# MCU.net
KiCad netlist of a schematic drawn in Altium Designer
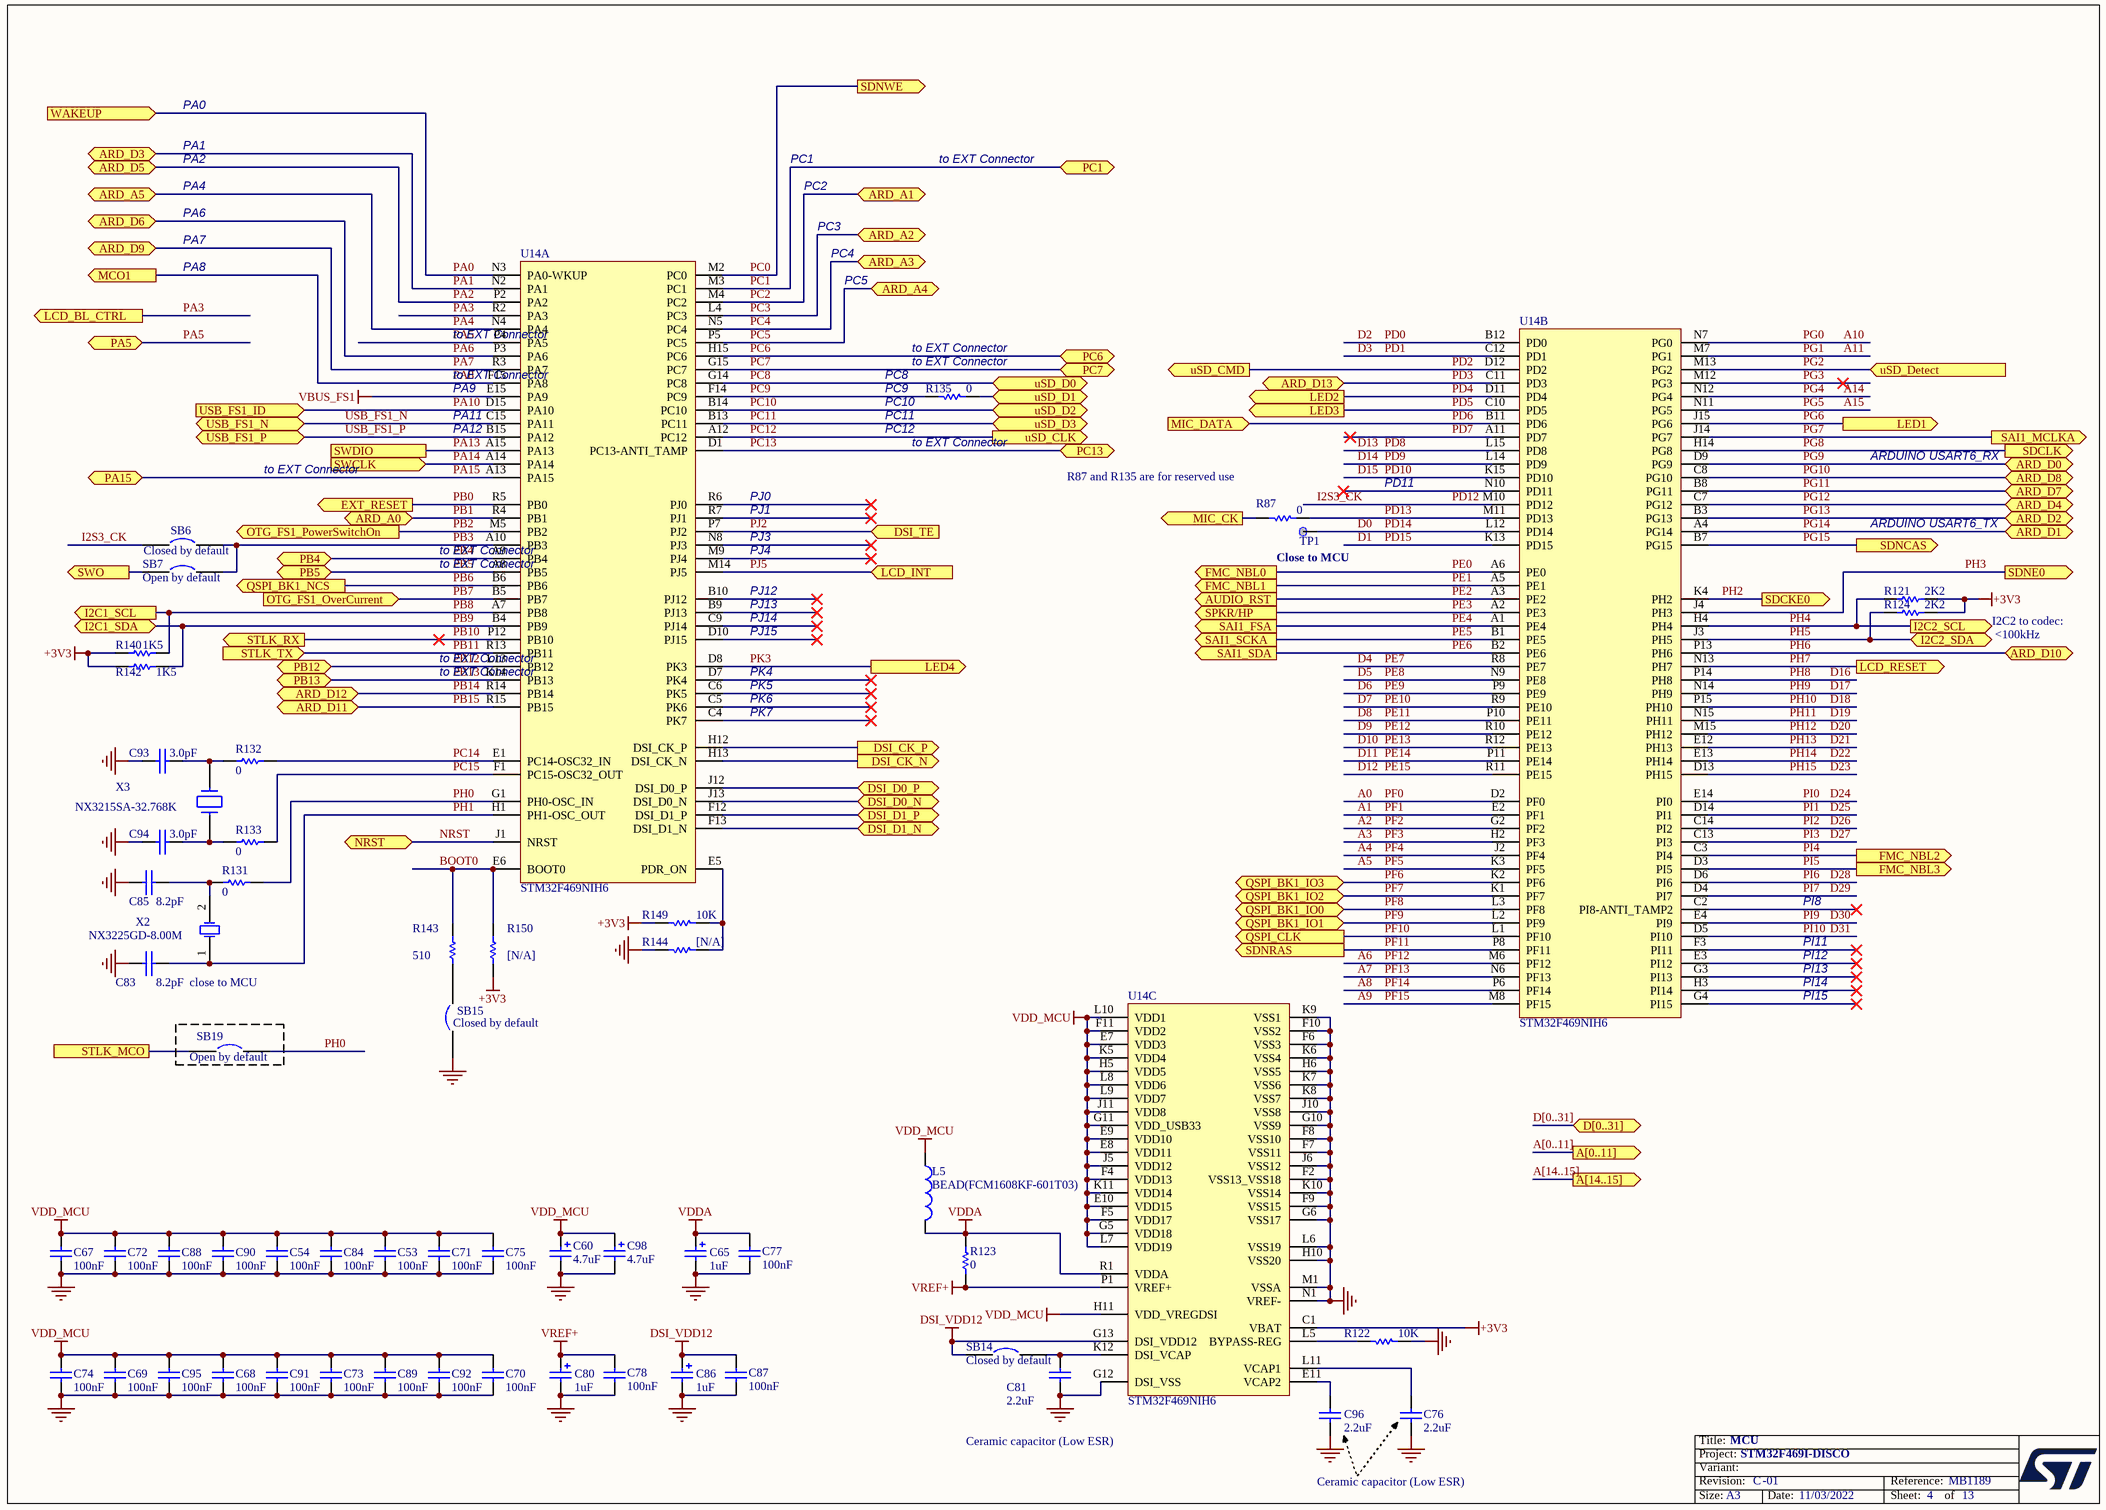
[diagram p0: MCU.SchDoc]

(export (version "E")
  (design (tool "Eeschema 10.0.6"))
  (components
    (comp (ref "C53")
      (value "100nF")
      (footprint "0402C")
      (description "Capacitor")
      (fields (field (name "PUBLISHER") "Altium Limited"))
      (libsource (lib "Miscellaneous Devices") (part "CAP"))
    )
    (comp (ref "C54")
      (value "100nF")
      (footprint "0402C")
      (description "Capacitor")
      (fields (field (name "PUBLISHER") "Altium Limited"))
      (libsource (lib "Miscellaneous Devices") (part "CAP"))
    )
    (comp (ref "C60")
      (value "4.7uF")
      (footprint "CPOL_TAJ-A_1206_H180")
      (description "Capacitor, Tantalum, 4.7uF, 16V, 10%, 4ohms, pkg Type_A (3216 metric), T=1.6mm")
      (libsource (lib "MB1189") (part "Cap_TAJA475K016R"))
    )
    (comp (ref "C65")
      (value "1uF")
      (footprint "CPOL_TAJ-A_1206_H180")
      (description "Capacitor, Tantalum, 1uF, 16V, 10%, 11Ohms, pkg Type_A (3216 metric), T=1.6mm")
      (libsource (lib "MB1189") (part "Cap_TAJA105K016RNJ"))
    )
    (comp (ref "C67")
      (value "100nF")
      (footprint "0402C")
      (description "Capacitor")
      (fields (field (name "PUBLISHER") "Altium Limited"))
      (libsource (lib "Miscellaneous Devices") (part "CAP"))
    )
    (comp (ref "C68")
      (value "100nF")
      (footprint "0402C")
      (description "Capacitor")
      (fields (field (name "PUBLISHER") "Altium Limited"))
      (libsource (lib "Miscellaneous Devices") (part "CAP"))
    )
    (comp (ref "C69")
      (value "100nF")
      (footprint "0402C")
      (description "Capacitor")
      (fields (field (name "PUBLISHER") "Altium Limited"))
      (libsource (lib "Miscellaneous Devices") (part "CAP"))
    )
    (comp (ref "C70")
      (value "100nF")
      (footprint "0402C")
      (description "Capacitor")
      (fields (field (name "PUBLISHER") "Altium Limited"))
      (libsource (lib "Miscellaneous Devices") (part "CAP"))
    )
    (comp (ref "C71")
      (value "100nF")
      (footprint "0402C")
      (description "Capacitor")
      (fields (field (name "PUBLISHER") "Altium Limited"))
      (libsource (lib "Miscellaneous Devices") (part "CAP"))
    )
    (comp (ref "C72")
      (value "100nF")
      (footprint "0402C")
      (description "Capacitor")
      (fields (field (name "PUBLISHER") "Altium Limited"))
      (libsource (lib "Miscellaneous Devices") (part "CAP"))
    )
    (comp (ref "C73")
      (value "100nF")
      (footprint "0402C")
      (description "Capacitor")
      (fields (field (name "PUBLISHER") "Altium Limited"))
      (libsource (lib "Miscellaneous Devices") (part "CAP"))
    )
    (comp (ref "C74")
      (value "100nF")
      (footprint "0402C")
      (description "Capacitor")
      (fields (field (name "PUBLISHER") "Altium Limited"))
      (libsource (lib "Miscellaneous Devices") (part "CAP"))
    )
    (comp (ref "C75")
      (value "100nF")
      (footprint "0402C")
      (description "Capacitor")
      (fields (field (name "PUBLISHER") "Altium Limited"))
      (libsource (lib "Miscellaneous Devices") (part "CAP"))
    )
    (comp (ref "C76")
      (value "2.2uF")
      (footprint "1206C")
      (description "Capacitor")
      (fields (field (name "PUBLISHER") "Altium Limited"))
      (libsource (lib "Miscellaneous Devices") (part "Cap"))
    )
    (comp (ref "C77")
      (value "100nF")
      (footprint "0402C")
      (description "Capacitor")
      (fields (field (name "PUBLISHER") "Altium Limited"))
      (libsource (lib "Miscellaneous Devices") (part "Cap"))
    )
    (comp (ref "C78")
      (value "100nF")
      (footprint "0402C")
      (description "Capacitor")
      (fields (field (name "PUBLISHER") "Altium Limited"))
      (libsource (lib "Miscellaneous Devices") (part "Cap"))
    )
    (comp (ref "C80")
      (value "1uF")
      (footprint "CPOL_TAJ-A_1206_H180")
      (description "Capacitor, Tantalum, 1uF, 16V, 10%, 11Ohms, pkg Type_A (3216 metric), T=1.6mm")
      (libsource (lib "MB1189") (part "Cap_TAJA105K016RNJ"))
    )
    (comp (ref "C81")
      (value "2.2uF")
      (footprint "1206C")
      (description "Capacitor")
      (fields (field (name "PUBLISHER") "Altium Limited"))
      (libsource (lib "Miscellaneous Devices") (part "Cap"))
    )
    (comp (ref "C83")
      (value "8.2pF")
      (footprint "0603C")
      (description "Capacitor")
      (libsource (lib "*") (part "CAP"))
    )
    (comp (ref "C84")
      (value "100nF")
      (footprint "0402C")
      (description "Capacitor")
      (fields (field (name "PUBLISHER") "Altium Limited"))
      (libsource (lib "Miscellaneous Devices") (part "CAP"))
    )
    (comp (ref "C85")
      (value "8.2pF")
      (footprint "0603C")
      (description "Capacitor")
      (libsource (lib "*") (part "CAP"))
    )
    (comp (ref "C86")
      (value "1uF")
      (footprint "CPOL_TAJ-A_1206_H180")
      (description "Capacitor, Tantalum, 1uF, 16V, 10%, 11Ohms, pkg Type_A (3216 metric), T=1.6mm")
      (libsource (lib "MB1189") (part "Cap_TAJA105K016RNJ"))
    )
    (comp (ref "C87")
      (value "100nF")
      (footprint "0402C")
      (description "Capacitor")
      (fields (field (name "PUBLISHER") "Altium Limited"))
      (libsource (lib "Miscellaneous Devices") (part "Cap"))
    )
    (comp (ref "C88")
      (value "100nF")
      (footprint "0402C")
      (description "Capacitor")
      (fields (field (name "PUBLISHER") "Altium Limited"))
      (libsource (lib "Miscellaneous Devices") (part "CAP"))
    )
    (comp (ref "C89")
      (value "100nF")
      (footprint "0402C")
      (description "Capacitor")
      (fields (field (name "PUBLISHER") "Altium Limited"))
      (libsource (lib "Miscellaneous Devices") (part "CAP"))
    )
    (comp (ref "C90")
      (value "100nF")
      (footprint "0402C")
      (description "Capacitor")
      (fields (field (name "PUBLISHER") "Altium Limited"))
      (libsource (lib "Miscellaneous Devices") (part "CAP"))
    )
    (comp (ref "C91")
      (value "100nF")
      (footprint "0402C")
      (description "Capacitor")
      (fields (field (name "PUBLISHER") "Altium Limited"))
      (libsource (lib "Miscellaneous Devices") (part "CAP"))
    )
    (comp (ref "C92")
      (value "100nF")
      (footprint "0402C")
      (description "Capacitor")
      (fields (field (name "PUBLISHER") "Altium Limited"))
      (libsource (lib "Miscellaneous Devices") (part "CAP"))
    )
    (comp (ref "C93")
      (value "3.0pF")
      (footprint "0603C")
      (description "Capacitor")
      (libsource (lib "") (part "CAP_1"))
    )
    (comp (ref "C94")
      (value "3.0pF")
      (footprint "0603C")
      (description "Capacitor")
      (libsource (lib "") (part "CAP_1"))
    )
    (comp (ref "C95")
      (value "100nF")
      (footprint "0402C")
      (description "Capacitor")
      (fields (field (name "PUBLISHER") "Altium Limited"))
      (libsource (lib "Miscellaneous Devices") (part "CAP"))
    )
    (comp (ref "C96")
      (value "2.2uF")
      (footprint "1206C")
      (description "Capacitor")
      (fields (field (name "PUBLISHER") "Altium Limited"))
      (libsource (lib "Miscellaneous Devices") (part "Cap"))
    )
    (comp (ref "C98")
      (value "4.7uF")
      (footprint "CPOL_TAJ-A_1206_H180")
      (description "Capacitor, Tantalum, 4.7uF, 16V, 10%, 4ohms, pkg Type_A (3216 metric), T=1.6mm")
      (libsource (lib "MB1189") (part "Cap_TAJA475K016R"))
    )
    (comp (ref "L5")
      (value "BEAD(FCM1608KF-601T03)")
      (footprint "0603L")
      (description "Inductor")
      (fields (field (name "PUBLISHER") "Altium Limited"))
      (libsource (lib "Miscellaneous Devices") (part "Inductor"))
    )
    (comp (ref "R87")
      (value "0")
      (footprint "0603R")
      (description "Resistor")
      (fields (field (name "PUBLISHER") "Altium Limited"))
      (libsource (lib "Miscellaneous Devices") (part "Res1"))
    )
    (comp (ref "R121")
      (value "2K2")
      (footprint "0603R")
      (description "Resistor")
      (fields (field (name "PUBLISHER") "Altium Limited"))
      (libsource (lib "") (part "Res1_1"))
    )
    (comp (ref "R122")
      (value "10K")
      (footprint "0402R")
      (description "Resistor")
      (fields (field (name "PUBLISHER") "Altium Limited"))
      (libsource (lib "") (part "Res1_1"))
    )
    (comp (ref "R123")
      (value "0")
      (footprint "0603R")
      (description "Resistor")
      (fields (field (name "PUBLISHER") "Altium Limited"))
      (libsource (lib "Miscellaneous Devices") (part "Res1"))
    )
    (comp (ref "R124")
      (value "2K2")
      (footprint "0603R")
      (description "Resistor")
      (fields (field (name "PUBLISHER") "Altium Limited"))
      (libsource (lib "") (part "Res1_1"))
    )
    (comp (ref "R131")
      (value "0")
      (footprint "0603R")
      (description "Resistor")
      (fields (field (name "PUBLISHER") "Altium Limited"))
      (libsource (lib "Miscellaneous Devices") (part "Res1"))
    )
    (comp (ref "R132")
      (value "0")
      (footprint "0603R")
      (description "Resistor")
      (fields (field (name "PUBLISHER") "Altium Limited"))
      (libsource (lib "") (part "Res1_1"))
    )
    (comp (ref "R133")
      (value "0")
      (footprint "0603R")
      (description "Resistor")
      (fields (field (name "PUBLISHER") "Altium Limited"))
      (libsource (lib "") (part "Res1_1"))
    )
    (comp (ref "R135")
      (value "0")
      (footprint "0603R")
      (description "Resistor")
      (fields (field (name "PUBLISHER") "Altium Limited"))
      (libsource (lib "Miscellaneous Devices") (part "Res1"))
    )
    (comp (ref "R140")
      (value "1K5")
      (footprint "0603R")
      (description "Resistor")
      (fields (field (name "PUBLISHER") "Altium Limited"))
      (libsource (lib "") (part "Res1_1"))
    )
    (comp (ref "R142")
      (value "1K5")
      (footprint "0603R")
      (description "Resistor")
      (fields (field (name "PUBLISHER") "Altium Limited"))
      (libsource (lib "") (part "Res1_1"))
    )
    (comp (ref "R143")
      (value "510")
      (footprint "0603R")
      (description "Resistor")
      (fields (field (name "PUBLISHER") "Altium Limited"))
      (libsource (lib "Miscellaneous Devices") (part "res1"))
    )
    (comp (ref "R144")
      (value "[N/A]")
      (footprint "0603R")
      (description "Resistor")
      (fields (field (name "PUBLISHER") "Altium Limited"))
      (libsource (lib "Miscellaneous Devices") (part "Res1"))
    )
    (comp (ref "R149")
      (value "10K")
      (footprint "0402R")
      (description "Resistor")
      (fields (field (name "PUBLISHER") "Altium Limited"))
      (libsource (lib "Miscellaneous Devices") (part "Res1"))
    )
    (comp (ref "R150")
      (value "[N/A]")
      (footprint "0603R")
      (description "Resistor")
      (fields (field (name "PUBLISHER") "Altium Limited"))
      (libsource (lib "Miscellaneous Devices") (part "res1"))
    )
    (comp (ref "SB6")
      (value "Closed by default")
      (footprint "SB_0603")
      (description "Circuit Breaker")
      (fields (field (name "PUBLISHER") "Altium Limited"))
      (libsource (lib "Miscellaneous Devices") (part "Circuit Breaker"))
    )
    (comp (ref "SB7")
      (value "Open by default")
      (footprint "SB_0603")
      (description "Circuit Breaker")
      (fields (field (name "PUBLISHER") "Altium Limited"))
      (libsource (lib "Miscellaneous Devices") (part "Circuit Breaker"))
    )
    (comp (ref "SB14")
      (value "Closed by default")
      (footprint "SB_0603")
      (description "Circuit Breaker")
      (fields (field (name "PUBLISHER") "Altium Limited"))
      (libsource (lib "Miscellaneous Devices") (part "Circuit Breaker"))
    )
    (comp (ref "SB15")
      (value "Closed by default")
      (footprint "SB_0603")
      (description "Circuit Breaker")
      (fields (field (name "PUBLISHER") "Altium Limited"))
      (libsource (lib "Miscellaneous Devices") (part "Circuit Breaker"))
    )
    (comp (ref "SB19")
      (value "Open by default")
      (footprint "SB_0603")
      (description "Circuit Breaker")
      (fields (field (name "PUBLISHER") "Altium Limited"))
      (libsource (lib "Miscellaneous Devices") (part "Circuit Breaker"))
    )
    (comp (ref "TP1") (value "TP") (footprint "TP_C40") (libsource (lib "Almos") (part "TP")))
    (comp (ref "U14")
      (value "STM32F469NIH6")
      (footprint "BGA216_0R8_13X13")
      (libsource (lib "MB1165") (part "Manta_Dragon_TFBGA216"))
    )
    (comp (ref "X2")
      (value "NX3225GD-8.00M")
      (footprint "XTAL_2SM_3R2X2R5_H1")
      (description "Crystal 8Mhz, 8pF, -+50PPM, SMD")
      (libsource (lib "MCD_TOOLS") (part "XTAL_8M_NX3225GD"))
    )
    (comp (ref "X3")
      (value "NX3215SA-32.768K")
      (footprint "XTAL_2SM_3R2X1R5")
      (description "Crystal 32.768kHz, 6pF, -+20PPM, R=50K, SMD")
      (libsource (lib "MCD_TOOLS") (part "XTAL_32K_NX3215SA"))
    )
  )
  (nets
    (net (code "1") (name "+3V3") (class "Default")
      (node (ref "R121") (pin "1") (pinfunction "1_1") (pintype "passive"))
      (node (ref "R124") (pin "1") (pinfunction "1_1") (pintype "passive"))
      (node (ref "R140") (pin "1") (pinfunction "1_1") (pintype "passive"))
      (node (ref "R142") (pin "1") (pinfunction "1_1") (pintype "passive"))
      (node (ref "R149") (pin "2") (pinfunction "2_2") (pintype "passive"))
      (node (ref "R150") (pin "2") (pinfunction "2_2") (pintype "passive"))
      (node (ref "U14") (pin "C1") (pinfunction "VBAT_C1") (pintype "passive"))
    )
    (net (code "2") (name "/A0") (class "Default")
      (node (ref "U14") (pin "D2") (pinfunction "PF0_D2") (pintype "passive"))
    )
    (net (code "3") (name "/A1") (class "Default")
      (node (ref "U14") (pin "E2") (pinfunction "PF1_E2") (pintype "passive"))
    )
    (net (code "4") (name "/A2") (class "Default")
      (node (ref "U14") (pin "G2") (pinfunction "PF2_G2") (pintype "passive"))
    )
    (net (code "5") (name "/A3") (class "Default")
      (node (ref "U14") (pin "H2") (pinfunction "PF3_H2") (pintype "passive"))
    )
    (net (code "6") (name "/A4") (class "Default")
      (node (ref "U14") (pin "J2") (pinfunction "PF4_J2") (pintype "passive"))
    )
    (net (code "7") (name "/A5") (class "Default")
      (node (ref "U14") (pin "K3") (pinfunction "PF5_K3") (pintype "passive"))
    )
    (net (code "8") (name "/A6") (class "Default")
      (node (ref "U14") (pin "M6") (pinfunction "PF12_M6") (pintype "passive"))
    )
    (net (code "9") (name "/A7") (class "Default")
      (node (ref "U14") (pin "N6") (pinfunction "PF13_N6") (pintype "passive"))
    )
    (net (code "10") (name "/A8") (class "Default")
      (node (ref "U14") (pin "P6") (pinfunction "PF14_P6") (pintype "passive"))
    )
    (net (code "11") (name "/A9") (class "Default")
      (node (ref "U14") (pin "M8") (pinfunction "PF15_M8") (pintype "passive"))
    )
    (net (code "12") (name "/A10") (class "Default")
      (node (ref "U14") (pin "N7") (pinfunction "PG0_N7") (pintype "passive"))
    )
    (net (code "13") (name "/A11") (class "Default")
      (node (ref "U14") (pin "M7") (pinfunction "PG1_M7") (pintype "passive"))
    )
    (net (code "14") (name "/A14") (class "Default")
      (node (ref "U14") (pin "N12") (pinfunction "PG4_N12") (pintype "passive"))
    )
    (net (code "15") (name "/A15") (class "Default")
      (node (ref "U14") (pin "N11") (pinfunction "PG5_N11") (pintype "passive"))
    )
    (net (code "18") (name "/BOOT0") (class "Default")
      (node (ref "R143") (pin "1") (pinfunction "1_1") (pintype "passive"))
      (node (ref "R150") (pin "1") (pinfunction "1_1") (pintype "passive"))
      (node (ref "U14") (pin "E6") (pinfunction "BOOT0_E6") (pintype "passive"))
    )
    (net (code "19") (name "/D0") (class "Default")
      (node (ref "TP1") (pin "1") (pinfunction "1_1") (pintype "passive"))
      (node (ref "U14") (pin "L12") (pinfunction "PD14_L12") (pintype "passive"))
    )
    (net (code "20") (name "/D1") (class "Default")
      (node (ref "U14") (pin "K13") (pinfunction "PD15_K13") (pintype "passive"))
    )
    (net (code "21") (name "/D2") (class "Default")
      (node (ref "U14") (pin "B12") (pinfunction "PD0_B12") (pintype "passive"))
    )
    (net (code "22") (name "/D3") (class "Default")
      (node (ref "U14") (pin "C12") (pinfunction "PD1_C12") (pintype "passive"))
    )
    (net (code "23") (name "/D4") (class "Default")
      (node (ref "U14") (pin "R8") (pinfunction "PE7_R8") (pintype "passive"))
    )
    (net (code "24") (name "/D5") (class "Default")
      (node (ref "U14") (pin "N9") (pinfunction "PE8_N9") (pintype "passive"))
    )
    (net (code "25") (name "/D6") (class "Default")
      (node (ref "U14") (pin "P9") (pinfunction "PE9_P9") (pintype "passive"))
    )
    (net (code "26") (name "/D7") (class "Default")
      (node (ref "U14") (pin "R9") (pinfunction "PE10_R9") (pintype "passive"))
    )
    (net (code "27") (name "/D8") (class "Default")
      (node (ref "U14") (pin "P10") (pinfunction "PE11_P10") (pintype "passive"))
    )
    (net (code "28") (name "/D9") (class "Default")
      (node (ref "U14") (pin "R10") (pinfunction "PE12_R10") (pintype "passive"))
    )
    (net (code "29") (name "/D10") (class "Default")
      (node (ref "U14") (pin "R12") (pinfunction "PE13_R12") (pintype "passive"))
    )
    (net (code "30") (name "/D11") (class "Default")
      (node (ref "U14") (pin "P11") (pinfunction "PE14_P11") (pintype "passive"))
    )
    (net (code "31") (name "/D12") (class "Default")
      (node (ref "U14") (pin "R11") (pinfunction "PE15_R11") (pintype "passive"))
    )
    (net (code "32") (name "/D13") (class "Default")
      (node (ref "U14") (pin "L15") (pinfunction "PD8_L15") (pintype "passive"))
    )
    (net (code "33") (name "/D14") (class "Default")
      (node (ref "U14") (pin "L14") (pinfunction "PD9_L14") (pintype "passive"))
    )
    (net (code "34") (name "/D15") (class "Default")
      (node (ref "U14") (pin "K15") (pinfunction "PD10_K15") (pintype "passive"))
    )
    (net (code "35") (name "/D16") (class "Default")
      (node (ref "U14") (pin "P14") (pinfunction "PH8_P14") (pintype "passive"))
    )
    (net (code "36") (name "/D17") (class "Default")
      (node (ref "U14") (pin "N14") (pinfunction "PH9_N14") (pintype "passive"))
    )
    (net (code "37") (name "/D18") (class "Default")
      (node (ref "U14") (pin "P15") (pinfunction "PH10_P15") (pintype "passive"))
    )
    (net (code "38") (name "/D19") (class "Default")
      (node (ref "U14") (pin "N15") (pinfunction "PH11_N15") (pintype "passive"))
    )
    (net (code "39") (name "/D20") (class "Default")
      (node (ref "U14") (pin "M15") (pinfunction "PH12_M15") (pintype "passive"))
    )
    (net (code "40") (name "/D21") (class "Default")
      (node (ref "U14") (pin "E12") (pinfunction "PH13_E12") (pintype "passive"))
    )
    (net (code "41") (name "/D22") (class "Default")
      (node (ref "U14") (pin "E13") (pinfunction "PH14_E13") (pintype "passive"))
    )
    (net (code "42") (name "/D23") (class "Default")
      (node (ref "U14") (pin "D13") (pinfunction "PH15_D13") (pintype "passive"))
    )
    (net (code "43") (name "/D24") (class "Default")
      (node (ref "U14") (pin "E14") (pinfunction "PI0_E14") (pintype "passive"))
    )
    (net (code "44") (name "/D25") (class "Default")
      (node (ref "U14") (pin "D14") (pinfunction "PI1_D14") (pintype "passive"))
    )
    (net (code "45") (name "/D26") (class "Default")
      (node (ref "U14") (pin "C14") (pinfunction "PI2_C14") (pintype "passive"))
    )
    (net (code "46") (name "/D27") (class "Default")
      (node (ref "U14") (pin "C13") (pinfunction "PI3_C13") (pintype "passive"))
    )
    (net (code "47") (name "/D28") (class "Default")
      (node (ref "U14") (pin "D6") (pinfunction "PI6_D6") (pintype "passive"))
    )
    (net (code "48") (name "/D29") (class "Default")
      (node (ref "U14") (pin "D4") (pinfunction "PI7_D4") (pintype "passive"))
    )
    (net (code "49") (name "/D30") (class "Default")
      (node (ref "U14") (pin "E4") (pinfunction "PI9_E4") (pintype "passive"))
    )
    (net (code "50") (name "/D31") (class "Default")
      (node (ref "U14") (pin "D5") (pinfunction "PI10_D5") (pintype "passive"))
    )
    (net (code "51") (name "/DSI_CK_N") (class "Default")
      (node (ref "U14") (pin "H13") (pinfunction "DSI_CK_N_H13") (pintype "passive"))
    )
    (net (code "52") (name "/DSI_CK_P") (class "Default")
      (node (ref "U14") (pin "H12") (pinfunction "DSI_CK_P_H12") (pintype "passive"))
    )
    (net (code "53") (name "/DSI_D0_N") (class "Default")
      (node (ref "U14") (pin "J13") (pinfunction "DSI_D0_N_J13") (pintype "passive"))
    )
    (net (code "54") (name "/DSI_D0_P") (class "Default")
      (node (ref "U14") (pin "J12") (pinfunction "DSI_D0_P_J12") (pintype "passive"))
    )
    (net (code "55") (name "/DSI_D1_N") (class "Default")
      (node (ref "U14") (pin "F13") (pinfunction "DSI_D1_N_F13") (pintype "passive"))
    )
    (net (code "56") (name "/DSI_D1_P") (class "Default")
      (node (ref "U14") (pin "F12") (pinfunction "DSI_D1_P_F12") (pintype "passive"))
    )
    (net (code "58") (name "/I2S3_CK") (class "Default")
      (node (ref "SB6") (pin "1") (pinfunction "1_1") (pintype "passive"))
      (node (ref "U14") (pin "M10") (pinfunction "PD12_M10") (pintype "passive"))
    )
    (net (code "59") (name "/MIC_CK") (class "Default")
      (node (ref "R87") (pin "1") (pinfunction "1_1") (pintype "passive"))
    )
    (net (code "60") (name "/NRST") (class "Default")
      (node (ref "U14") (pin "J1") (pinfunction "NRST_J1") (pintype "passive"))
    )
    (net (code "61") (name "/PA0") (class "Default")
      (node (ref "U14") (pin "N3") (pinfunction "PA0-WKUP_N3") (pintype "passive"))
    )
    (net (code "62") (name "/PA1") (class "Default")
      (node (ref "U14") (pin "N2") (pinfunction "PA1_N2") (pintype "passive"))
    )
    (net (code "63") (name "/PA2") (class "Default")
      (node (ref "U14") (pin "P2") (pinfunction "PA2_P2") (pintype "passive"))
    )
    (net (code "64") (name "/PA3") (class "Default")
      (node (ref "U14") (pin "R2") (pinfunction "PA3_R2") (pintype "passive"))
    )
    (net (code "65") (name "/PA4") (class "Default")
      (node (ref "U14") (pin "N4") (pinfunction "PA4_N4") (pintype "passive"))
    )
    (net (code "66") (name "/PA5") (class "Default")
      (node (ref "U14") (pin "P4") (pinfunction "PA5_P4") (pintype "passive"))
    )
    (net (code "67") (name "/PA6") (class "Default")
      (node (ref "U14") (pin "P3") (pinfunction "PA6_P3") (pintype "passive"))
    )
    (net (code "68") (name "/PA7") (class "Default")
      (node (ref "U14") (pin "R3") (pinfunction "PA7_R3") (pintype "passive"))
    )
    (net (code "69") (name "/PA8") (class "Default")
      (node (ref "U14") (pin "F15") (pinfunction "PA8_F15") (pintype "passive"))
    )
    (net (code "70") (name "/PA10") (class "Default")
      (node (ref "U14") (pin "D15") (pinfunction "PA10_D15") (pintype "passive"))
    )
    (net (code "71") (name "/PA13") (class "Default")
      (node (ref "U14") (pin "A15") (pinfunction "PA13_A15") (pintype "passive"))
    )
    (net (code "72") (name "/PA14") (class "Default")
      (node (ref "U14") (pin "A14") (pinfunction "PA14_A14") (pintype "passive"))
    )
    (net (code "73") (name "/PA15") (class "Default")
      (node (ref "U14") (pin "A13") (pinfunction "PA15_A13") (pintype "passive"))
    )
    (net (code "74") (name "/PB0") (class "Default")
      (node (ref "U14") (pin "R5") (pinfunction "PB0_R5") (pintype "passive"))
    )
    (net (code "75") (name "/PB1") (class "Default")
      (node (ref "U14") (pin "R4") (pinfunction "PB1_R4") (pintype "passive"))
    )
    (net (code "76") (name "/PB2") (class "Default")
      (node (ref "U14") (pin "M5") (pinfunction "PB2_M5") (pintype "passive"))
    )
    (net (code "77") (name "/PB3") (class "Default")
      (node (ref "SB6") (pin "2") (pinfunction "2_2") (pintype "passive"))
      (node (ref "SB7") (pin "2") (pinfunction "2_2") (pintype "passive"))
      (node (ref "U14") (pin "A10") (pinfunction "PB3_A10") (pintype "passive"))
    )
    (net (code "78") (name "/PB4") (class "Default")
      (node (ref "U14") (pin "A9") (pinfunction "PB4_A9") (pintype "passive"))
    )
    (net (code "79") (name "/PB5") (class "Default")
      (node (ref "U14") (pin "A8") (pinfunction "PB5_A8") (pintype "passive"))
    )
    (net (code "80") (name "/PB6") (class "Default")
      (node (ref "U14") (pin "B6") (pinfunction "PB6_B6") (pintype "passive"))
    )
    (net (code "81") (name "/PB7") (class "Default")
      (node (ref "U14") (pin "B5") (pinfunction "PB7_B5") (pintype "passive"))
    )
    (net (code "82") (name "/PB8") (class "Default")
      (node (ref "R140") (pin "2") (pinfunction "2_2") (pintype "passive"))
      (node (ref "U14") (pin "A7") (pinfunction "PB8_A7") (pintype "passive"))
    )
    (net (code "83") (name "/PB9") (class "Default")
      (node (ref "R142") (pin "2") (pinfunction "2_2") (pintype "passive"))
      (node (ref "U14") (pin "B4") (pinfunction "PB9_B4") (pintype "passive"))
    )
    (net (code "84") (name "/PB10") (class "Default")
      (node (ref "U14") (pin "P12") (pinfunction "PB10_P12") (pintype "passive"))
    )
    (net (code "85") (name "/PB11") (class "Default")
      (node (ref "U14") (pin "R13") (pinfunction "PB11_R13") (pintype "passive"))
    )
    (net (code "86") (name "/PB12") (class "Default")
      (node (ref "U14") (pin "L13") (pinfunction "PB12_L13") (pintype "passive"))
    )
    (net (code "87") (name "/PB13") (class "Default")
      (node (ref "U14") (pin "K14") (pinfunction "PB13_K14") (pintype "passive"))
    )
    (net (code "88") (name "/PB14") (class "Default")
      (node (ref "U14") (pin "R14") (pinfunction "PB14_R14") (pintype "passive"))
    )
    (net (code "89") (name "/PB15") (class "Default")
      (node (ref "U14") (pin "R15") (pinfunction "PB15_R15") (pintype "passive"))
    )
    (net (code "90") (name "/PC0") (class "Default")
      (node (ref "U14") (pin "M2") (pinfunction "PC0_M2") (pintype "passive"))
    )
    (net (code "91") (name "/PC1") (class "Default")
      (node (ref "U14") (pin "M3") (pinfunction "PC1_M3") (pintype "passive"))
    )
    (net (code "92") (name "/PC2") (class "Default")
      (node (ref "U14") (pin "M4") (pinfunction "PC2_M4") (pintype "passive"))
    )
    (net (code "93") (name "/PC3") (class "Default")
      (node (ref "U14") (pin "L4") (pinfunction "PC3_L4") (pintype "passive"))
    )
    (net (code "94") (name "/PC4") (class "Default")
      (node (ref "U14") (pin "N5") (pinfunction "PC4_N5") (pintype "passive"))
    )
    (net (code "95") (name "/PC5") (class "Default")
      (node (ref "U14") (pin "P5") (pinfunction "PC5_P5") (pintype "passive"))
    )
    (net (code "96") (name "/PC6") (class "Default")
      (node (ref "U14") (pin "H15") (pinfunction "PC6_H15") (pintype "passive"))
    )
    (net (code "97") (name "/PC7") (class "Default")
      (node (ref "U14") (pin "G15") (pinfunction "PC7_G15") (pintype "passive"))
    )
    (net (code "98") (name "/PC8") (class "Default")
      (node (ref "U14") (pin "G14") (pinfunction "PC8_G14") (pintype "passive"))
    )
    (net (code "99") (name "/PC9") (class "Default")
      (node (ref "R135") (pin "1") (pinfunction "1_1") (pintype "passive"))
      (node (ref "U14") (pin "F14") (pinfunction "PC9_F14") (pintype "passive"))
    )
    (net (code "100") (name "/PC10") (class "Default")
      (node (ref "U14") (pin "B14") (pinfunction "PC10_B14") (pintype "passive"))
    )
    (net (code "101") (name "/PC11") (class "Default")
      (node (ref "U14") (pin "B13") (pinfunction "PC11_B13") (pintype "passive"))
    )
    (net (code "102") (name "/PC12") (class "Default")
      (node (ref "U14") (pin "A12") (pinfunction "PC12_A12") (pintype "passive"))
    )
    (net (code "103") (name "/PC13") (class "Default")
      (node (ref "U14") (pin "D1") (pinfunction "PC13-ANTI_TAMP_D1") (pintype "passive"))
    )
    (net (code "104") (name "/PC14") (class "Default")
      (node (ref "R132") (pin "2") (pinfunction "2_2") (pintype "passive"))
      (node (ref "U14") (pin "E1") (pinfunction "PC14-OSC32_IN_E1") (pintype "passive"))
    )
    (net (code "105") (name "/PC15") (class "Default")
      (node (ref "R133") (pin "2") (pinfunction "2_2") (pintype "passive"))
      (node (ref "U14") (pin "F1") (pinfunction "PC15-OSC32_OUT_F1") (pintype "passive"))
    )
    (net (code "106") (name "/PD2") (class "Default")
      (node (ref "U14") (pin "D12") (pinfunction "PD2_D12") (pintype "passive"))
    )
    (net (code "107") (name "/PD3") (class "Default")
      (node (ref "U14") (pin "C11") (pinfunction "PD3_C11") (pintype "passive"))
    )
    (net (code "108") (name "/PD4") (class "Default")
      (node (ref "U14") (pin "D11") (pinfunction "PD4_D11") (pintype "passive"))
    )
    (net (code "109") (name "/PD5") (class "Default")
      (node (ref "U14") (pin "C10") (pinfunction "PD5_C10") (pintype "passive"))
    )
    (net (code "110") (name "/PD6") (class "Default")
      (node (ref "U14") (pin "B11") (pinfunction "PD6_B11") (pintype "passive"))
    )
    (net (code "111") (name "/PD7") (class "Default")
      (node (ref "U14") (pin "A11") (pinfunction "PD7_A11") (pintype "passive"))
    )
    (net (code "112") (name "/PD13") (class "Default")
      (node (ref "R87") (pin "2") (pinfunction "2_2") (pintype "passive"))
      (node (ref "U14") (pin "M11") (pinfunction "PD13_M11") (pintype "passive"))
    )
    (net (code "113") (name "/PE0") (class "Default")
      (node (ref "U14") (pin "A6") (pinfunction "PE0_A6") (pintype "passive"))
    )
    (net (code "114") (name "/PE1") (class "Default")
      (node (ref "U14") (pin "A5") (pinfunction "PE1_A5") (pintype "passive"))
    )
    (net (code "115") (name "/PE2") (class "Default")
      (node (ref "U14") (pin "A3") (pinfunction "PE2_A3") (pintype "passive"))
    )
    (net (code "116") (name "/PE3") (class "Default")
      (node (ref "U14") (pin "A2") (pinfunction "PE3_A2") (pintype "passive"))
    )
    (net (code "117") (name "/PE4") (class "Default")
      (node (ref "U14") (pin "A1") (pinfunction "PE4_A1") (pintype "passive"))
    )
    (net (code "118") (name "/PE5") (class "Default")
      (node (ref "U14") (pin "B1") (pinfunction "PE5_B1") (pintype "passive"))
    )
    (net (code "119") (name "/PE6") (class "Default")
      (node (ref "U14") (pin "B2") (pinfunction "PE6_B2") (pintype "passive"))
    )
    (net (code "120") (name "/PF6") (class "Default")
      (node (ref "U14") (pin "K2") (pinfunction "PF6_K2") (pintype "passive"))
    )
    (net (code "121") (name "/PF7") (class "Default")
      (node (ref "U14") (pin "K1") (pinfunction "PF7_K1") (pintype "passive"))
    )
    (net (code "122") (name "/PF8") (class "Default")
      (node (ref "U14") (pin "L3") (pinfunction "PF8_L3") (pintype "passive"))
    )
    (net (code "123") (name "/PF9") (class "Default")
      (node (ref "U14") (pin "L2") (pinfunction "PF9_L2") (pintype "passive"))
    )
    (net (code "124") (name "/PF10") (class "Default")
      (node (ref "U14") (pin "L1") (pinfunction "PF10_L1") (pintype "passive"))
    )
    (net (code "125") (name "/PF11") (class "Default")
      (node (ref "U14") (pin "P8") (pinfunction "PF11_P8") (pintype "passive"))
    )
    (net (code "126") (name "/PG2") (class "Default")
      (node (ref "U14") (pin "M13") (pinfunction "PG2_M13") (pintype "passive"))
    )
    (net (code "127") (name "/PG3") (class "Default")
      (node (ref "U14") (pin "M12") (pinfunction "PG3_M12") (pintype "passive"))
    )
    (net (code "128") (name "/PG6") (class "Default")
      (node (ref "U14") (pin "J15") (pinfunction "PG6_J15") (pintype "passive"))
    )
    (net (code "129") (name "/PG7") (class "Default")
      (node (ref "U14") (pin "J14") (pinfunction "PG7_J14") (pintype "passive"))
    )
    (net (code "130") (name "/PG8") (class "Default")
      (node (ref "U14") (pin "H14") (pinfunction "PG8_H14") (pintype "passive"))
    )
    (net (code "131") (name "/PG9") (class "Default")
      (node (ref "U14") (pin "D9") (pinfunction "PG9_D9") (pintype "passive"))
    )
    (net (code "132") (name "/PG10") (class "Default")
      (node (ref "U14") (pin "C8") (pinfunction "PG10_C8") (pintype "passive"))
    )
    (net (code "133") (name "/PG11") (class "Default")
      (node (ref "U14") (pin "B8") (pinfunction "PG11_B8") (pintype "passive"))
    )
    (net (code "134") (name "/PG12") (class "Default")
      (node (ref "U14") (pin "C7") (pinfunction "PG12_C7") (pintype "passive"))
    )
    (net (code "135") (name "/PG13") (class "Default")
      (node (ref "U14") (pin "B3") (pinfunction "PG13_B3") (pintype "passive"))
    )
    (net (code "136") (name "/PG14") (class "Default")
      (node (ref "U14") (pin "A4") (pinfunction "PG14_A4") (pintype "passive"))
    )
    (net (code "137") (name "/PG15") (class "Default")
      (node (ref "U14") (pin "B7") (pinfunction "PG15_B7") (pintype "passive"))
    )
    (net (code "138") (name "/PH0") (class "Default")
      (node (ref "R131") (pin "1") (pinfunction "1_1") (pintype "passive"))
      (node (ref "SB19") (pin "2") (pinfunction "2_2") (pintype "passive"))
      (node (ref "U14") (pin "G1") (pinfunction "PH0-OSC_IN_G1") (pintype "passive"))
    )
    (net (code "139") (name "/PH1") (class "Default")
      (node (ref "C83") (pin "1") (pinfunction "1_1") (pintype "passive"))
      (node (ref "U14") (pin "H1") (pinfunction "PH1-OSC_OUT_H1") (pintype "passive"))
      (node (ref "X2") (pin "1") (pinfunction "OSC1_1") (pintype "passive"))
    )
    (net (code "140") (name "/PH2") (class "Default")
      (node (ref "U14") (pin "K4") (pinfunction "PH2_K4") (pintype "passive"))
    )
    (net (code "141") (name "/PH3") (class "Default")
      (node (ref "U14") (pin "J4") (pinfunction "PH3_J4") (pintype "passive"))
    )
    (net (code "142") (name "/PH4") (class "Default")
      (node (ref "R121") (pin "2") (pinfunction "2_2") (pintype "passive"))
      (node (ref "U14") (pin "H4") (pinfunction "PH4_H4") (pintype "passive"))
    )
    (net (code "143") (name "/PH5") (class "Default")
      (node (ref "R124") (pin "2") (pinfunction "2_2") (pintype "passive"))
      (node (ref "U14") (pin "J3") (pinfunction "PH5_J3") (pintype "passive"))
    )
    (net (code "144") (name "/PH6") (class "Default")
      (node (ref "U14") (pin "P13") (pinfunction "PH6_P13") (pintype "passive"))
    )
    (net (code "145") (name "/PH7") (class "Default")
      (node (ref "U14") (pin "N13") (pinfunction "PH7_N13") (pintype "passive"))
    )
    (net (code "146") (name "/PI4") (class "Default")
      (node (ref "U14") (pin "C3") (pinfunction "PI4_C3") (pintype "passive"))
    )
    (net (code "147") (name "/PI5") (class "Default")
      (node (ref "U14") (pin "D3") (pinfunction "PI5_D3") (pintype "passive"))
    )
    (net (code "148") (name "/PJ2") (class "Default")
      (node (ref "U14") (pin "P7") (pinfunction "PJ2_P7") (pintype "passive"))
    )
    (net (code "149") (name "/PJ5") (class "Default")
      (node (ref "U14") (pin "M14") (pinfunction "PJ5_M14") (pintype "passive"))
    )
    (net (code "150") (name "/PK3") (class "Default")
      (node (ref "U14") (pin "D8") (pinfunction "PK3_D8") (pintype "passive"))
    )
    (net (code "151") (name "/STLK_MCO") (class "Default")
      (node (ref "SB19") (pin "1") (pinfunction "1_1") (pintype "passive"))
    )
    (net (code "152") (name "/SWO") (class "Default")
      (node (ref "SB7") (pin "1") (pinfunction "1_1") (pintype "passive"))
    )
    (net (code "153") (name "/USB_FS1_N") (class "Default")
      (node (ref "U14") (pin "C15") (pinfunction "PA11_C15") (pintype "passive"))
    )
    (net (code "154") (name "/USB_FS1_P") (class "Default")
      (node (ref "U14") (pin "B15") (pinfunction "PA12_B15") (pintype "passive"))
    )
    (net (code "155") (name "/uSD_D1") (class "Default")
      (node (ref "R135") (pin "2") (pinfunction "2_2") (pintype "passive"))
    )
    (net (code "156") (name "DSI_VDD12") (class "Default")
      (node (ref "C86") (pin "1") (pinfunction "1_1") (pintype "passive"))
      (node (ref "C87") (pin "2") (pinfunction "2_2") (pintype "passive"))
      (node (ref "SB14") (pin "1") (pinfunction "1_1") (pintype "passive"))
      (node (ref "U14") (pin "G13") (pinfunction "DSI_VDD12_G13") (pintype "passive"))
    )
    (net (code "157") (name "GND") (class "Default")
      (node (ref "C53") (pin "2") (pinfunction "2_2") (pintype "passive"))
      (node (ref "C54") (pin "2") (pinfunction "2_2") (pintype "passive"))
      (node (ref "C60") (pin "2") (pinfunction "2_2") (pintype "passive"))
      (node (ref "C65") (pin "2") (pinfunction "2_2") (pintype "passive"))
      (node (ref "C67") (pin "2") (pinfunction "2_2") (pintype "passive"))
      (node (ref "C68") (pin "2") (pinfunction "2_2") (pintype "passive"))
      (node (ref "C69") (pin "2") (pinfunction "2_2") (pintype "passive"))
      (node (ref "C70") (pin "2") (pinfunction "2_2") (pintype "passive"))
      (node (ref "C71") (pin "2") (pinfunction "2_2") (pintype "passive"))
      (node (ref "C72") (pin "2") (pinfunction "2_2") (pintype "passive"))
      (node (ref "C73") (pin "2") (pinfunction "2_2") (pintype "passive"))
      (node (ref "C74") (pin "2") (pinfunction "2_2") (pintype "passive"))
      (node (ref "C75") (pin "2") (pinfunction "2_2") (pintype "passive"))
      (node (ref "C76") (pin "2") (pinfunction "2_2") (pintype "passive"))
      (node (ref "C77") (pin "1") (pinfunction "1_1") (pintype "passive"))
      (node (ref "C78") (pin "1") (pinfunction "1_1") (pintype "passive"))
      (node (ref "C80") (pin "2") (pinfunction "2_2") (pintype "passive"))
      (node (ref "C81") (pin "2") (pinfunction "2_2") (pintype "passive"))
      (node (ref "C83") (pin "2") (pinfunction "2_2") (pintype "passive"))
      (node (ref "C84") (pin "2") (pinfunction "2_2") (pintype "passive"))
      (node (ref "C85") (pin "2") (pinfunction "2_2") (pintype "passive"))
      (node (ref "C86") (pin "2") (pinfunction "2_2") (pintype "passive"))
      (node (ref "C87") (pin "1") (pinfunction "1_1") (pintype "passive"))
      (node (ref "C88") (pin "2") (pinfunction "2_2") (pintype "passive"))
      (node (ref "C89") (pin "2") (pinfunction "2_2") (pintype "passive"))
      (node (ref "C90") (pin "2") (pinfunction "2_2") (pintype "passive"))
      (node (ref "C91") (pin "2") (pinfunction "2_2") (pintype "passive"))
      (node (ref "C92") (pin "2") (pinfunction "2_2") (pintype "passive"))
      (node (ref "C93") (pin "2") (pinfunction "2_2") (pintype "passive"))
      (node (ref "C94") (pin "2") (pinfunction "2_2") (pintype "passive"))
      (node (ref "C95") (pin "2") (pinfunction "2_2") (pintype "passive"))
      (node (ref "C96") (pin "2") (pinfunction "2_2") (pintype "passive"))
      (node (ref "C98") (pin "2") (pinfunction "2_2") (pintype "passive"))
      (node (ref "R122") (pin "1") (pinfunction "1_1") (pintype "passive"))
      (node (ref "R144") (pin "2") (pinfunction "2_2") (pintype "passive"))
      (node (ref "SB15") (pin "1") (pinfunction "1_1") (pintype "passive"))
      (node (ref "U14") (pin "F10") (pinfunction "VSS2_F10") (pintype "passive"))
      (node (ref "U14") (pin "F2") (pinfunction "VSS13_VSS18_F2") (pintype "passive"))
      (node (ref "U14") (pin "F6") (pinfunction "VSS3_F6") (pintype "passive"))
      (node (ref "U14") (pin "F7") (pinfunction "VSS11_F7") (pintype "passive"))
      (node (ref "U14") (pin "F8") (pinfunction "VSS10_F8") (pintype "passive"))
      (node (ref "U14") (pin "F9") (pinfunction "VSS15_F9") (pintype "passive"))
      (node (ref "U14") (pin "G10") (pinfunction "VSS9_G10") (pintype "passive"))
      (node (ref "U14") (pin "G12") (pinfunction "DSI_VSS_G12") (pintype "passive"))
      (node (ref "U14") (pin "G6") (pinfunction "VSS17_G6") (pintype "passive"))
      (node (ref "U14") (pin "H10") (pinfunction "VSS20_H10") (pintype "passive"))
      (node (ref "U14") (pin "H6") (pinfunction "VSS5_H6") (pintype "passive"))
      (node (ref "U14") (pin "J10") (pinfunction "VSS8_J10") (pintype "passive"))
      (node (ref "U14") (pin "J6") (pinfunction "VSS12_J6") (pintype "passive"))
      (node (ref "U14") (pin "K10") (pinfunction "VSS14_K10") (pintype "passive"))
      (node (ref "U14") (pin "K6") (pinfunction "VSS4_K6") (pintype "passive"))
      (node (ref "U14") (pin "K7") (pinfunction "VSS6_K7") (pintype "passive"))
      (node (ref "U14") (pin "K8") (pinfunction "VSS7_K8") (pintype "passive"))
      (node (ref "U14") (pin "K9") (pinfunction "VSS1_K9") (pintype "passive"))
      (node (ref "U14") (pin "L6") (pinfunction "VSS19_L6") (pintype "passive"))
      (node (ref "U14") (pin "M1") (pinfunction "VSSA_M1") (pintype "passive"))
      (node (ref "U14") (pin "N1") (pinfunction "VREF-_N1") (pintype "passive"))
    )
    (net (code "158") (name "Net-(C93-Pad1)") (class "Default")
      (node (ref "C93") (pin "1") (pinfunction "1_1") (pintype "passive"))
      (node (ref "R132") (pin "1") (pinfunction "1_1") (pintype "passive"))
      (node (ref "X3") (pin "1") (pinfunction "1_1") (pintype "passive"))
    )
    (net (code "159") (name "Net-(C94-Pad1)") (class "Default")
      (node (ref "C94") (pin "1") (pinfunction "1_1") (pintype "passive"))
      (node (ref "R133") (pin "1") (pinfunction "1_1") (pintype "passive"))
      (node (ref "X3") (pin "2") (pinfunction "2_2") (pintype "passive"))
    )
    (net (code "160") (name "Net-(R143-Pad2)") (class "Default")
      (node (ref "R143") (pin "2") (pinfunction "2_2") (pintype "passive"))
      (node (ref "SB15") (pin "2") (pinfunction "2_2") (pintype "passive"))
    )
    (net (code "161") (name "Net-(U14A-PDR_ON)") (class "Default")
      (node (ref "R144") (pin "1") (pinfunction "1_1") (pintype "passive"))
      (node (ref "R149") (pin "1") (pinfunction "1_1") (pintype "passive"))
      (node (ref "U14") (pin "E5") (pinfunction "PDR_ON_E5") (pintype "passive"))
    )
    (net (code "162") (name "Net-(U14C-BYPASS-REG)") (class "Default")
      (node (ref "R122") (pin "2") (pinfunction "2_2") (pintype "passive"))
      (node (ref "U14") (pin "L5") (pinfunction "BYPASS-REG_L5") (pintype "passive"))
    )
    (net (code "163") (name "Net-(U14C-DSI_VCAP)") (class "Default")
      (node (ref "C81") (pin "1") (pinfunction "1_1") (pintype "passive"))
      (node (ref "SB14") (pin "2") (pinfunction "2_2") (pintype "passive"))
      (node (ref "U14") (pin "K12") (pinfunction "DSI_VCAP_K12") (pintype "passive"))
    )
    (net (code "164") (name "Net-(U14C-VCAP1)") (class "Default")
      (node (ref "C76") (pin "1") (pinfunction "1_1") (pintype "passive"))
      (node (ref "U14") (pin "L11") (pinfunction "VCAP1_L11") (pintype "passive"))
    )
    (net (code "165") (name "Net-(U14C-VCAP2)") (class "Default")
      (node (ref "C96") (pin "1") (pinfunction "1_1") (pintype "passive"))
      (node (ref "U14") (pin "E11") (pinfunction "VCAP2_E11") (pintype "passive"))
    )
    (net (code "166") (name "Net-(X2-OSC2)") (class "Default")
      (node (ref "C85") (pin "1") (pinfunction "1_1") (pintype "passive"))
      (node (ref "R131") (pin "2") (pinfunction "2_2") (pintype "passive"))
      (node (ref "X2") (pin "2") (pinfunction "OSC2_2") (pintype "passive"))
    )
    (net (code "167") (name "VBUS_FS1") (class "Default")
      (node (ref "U14") (pin "E15") (pinfunction "PA9_E15") (pintype "passive"))
    )
    (net (code "168") (name "VDDA") (class "Default")
      (node (ref "C65") (pin "1") (pinfunction "1_1") (pintype "passive"))
      (node (ref "C77") (pin "2") (pinfunction "2_2") (pintype "passive"))
      (node (ref "L5") (pin "2") (pinfunction "2_2") (pintype "passive"))
      (node (ref "R123") (pin "1") (pinfunction "1_1") (pintype "passive"))
      (node (ref "U14") (pin "R1") (pinfunction "VDDA_R1") (pintype "passive"))
    )
    (net (code "169") (name "VDD_MCU") (class "Default")
      (node (ref "C53") (pin "1") (pinfunction "1_1") (pintype "passive"))
      (node (ref "C54") (pin "1") (pinfunction "1_1") (pintype "passive"))
      (node (ref "C60") (pin "1") (pinfunction "1_1") (pintype "passive"))
      (node (ref "C67") (pin "1") (pinfunction "1_1") (pintype "passive"))
      (node (ref "C68") (pin "1") (pinfunction "1_1") (pintype "passive"))
      (node (ref "C69") (pin "1") (pinfunction "1_1") (pintype "passive"))
      (node (ref "C70") (pin "1") (pinfunction "1_1") (pintype "passive"))
      (node (ref "C71") (pin "1") (pinfunction "1_1") (pintype "passive"))
      (node (ref "C72") (pin "1") (pinfunction "1_1") (pintype "passive"))
      (node (ref "C73") (pin "1") (pinfunction "1_1") (pintype "passive"))
      (node (ref "C74") (pin "1") (pinfunction "1_1") (pintype "passive"))
      (node (ref "C75") (pin "1") (pinfunction "1_1") (pintype "passive"))
      (node (ref "C84") (pin "1") (pinfunction "1_1") (pintype "passive"))
      (node (ref "C88") (pin "1") (pinfunction "1_1") (pintype "passive"))
      (node (ref "C89") (pin "1") (pinfunction "1_1") (pintype "passive"))
      (node (ref "C90") (pin "1") (pinfunction "1_1") (pintype "passive"))
      (node (ref "C91") (pin "1") (pinfunction "1_1") (pintype "passive"))
      (node (ref "C92") (pin "1") (pinfunction "1_1") (pintype "passive"))
      (node (ref "C95") (pin "1") (pinfunction "1_1") (pintype "passive"))
      (node (ref "C98") (pin "1") (pinfunction "1_1") (pintype "passive"))
      (node (ref "L5") (pin "1") (pinfunction "1_1") (pintype "passive"))
      (node (ref "U14") (pin "E10") (pinfunction "VDD15_E10") (pintype "passive"))
      (node (ref "U14") (pin "E7") (pinfunction "VDD3_E7") (pintype "passive"))
      (node (ref "U14") (pin "E8") (pinfunction "VDD11_E8") (pintype "passive"))
      (node (ref "U14") (pin "E9") (pinfunction "VDD10_E9") (pintype "passive"))
      (node (ref "U14") (pin "F11") (pinfunction "VDD2_F11") (pintype "passive"))
      (node (ref "U14") (pin "F4") (pinfunction "VDD13_F4") (pintype "passive"))
      (node (ref "U14") (pin "F5") (pinfunction "VDD17_F5") (pintype "passive"))
      (node (ref "U14") (pin "G11") (pinfunction "VDD_USB33_G11") (pintype "passive"))
      (node (ref "U14") (pin "G5") (pinfunction "VDD18_G5") (pintype "passive"))
      (node (ref "U14") (pin "H11") (pinfunction "VDD_VREGDSI_H11") (pintype "passive"))
      (node (ref "U14") (pin "H5") (pinfunction "VDD5_H5") (pintype "passive"))
      (node (ref "U14") (pin "J11") (pinfunction "VDD8_J11") (pintype "passive"))
      (node (ref "U14") (pin "J5") (pinfunction "VDD12_J5") (pintype "passive"))
      (node (ref "U14") (pin "K11") (pinfunction "VDD14_K11") (pintype "passive"))
      (node (ref "U14") (pin "K5") (pinfunction "VDD4_K5") (pintype "passive"))
      (node (ref "U14") (pin "L10") (pinfunction "VDD1_L10") (pintype "passive"))
      (node (ref "U14") (pin "L7") (pinfunction "VDD19_L7") (pintype "passive"))
      (node (ref "U14") (pin "L8") (pinfunction "VDD6_L8") (pintype "passive"))
      (node (ref "U14") (pin "L9") (pinfunction "VDD7_L9") (pintype "passive"))
    )
    (net (code "170") (name "VREF+") (class "Default")
      (node (ref "C78") (pin "2") (pinfunction "2_2") (pintype "passive"))
      (node (ref "C80") (pin "1") (pinfunction "1_1") (pintype "passive"))
      (node (ref "R123") (pin "2") (pinfunction "2_2") (pintype "passive"))
      (node (ref "U14") (pin "P1") (pinfunction "VREF+_P1") (pintype "passive"))
    )
    (net (code "171") (name "unconnected-(U14A-PJ0-PadR6)") (class "Default")
      (node (ref "U14") (pin "R6") (pinfunction "PJ0_R6") (pintype "passive+no_connect"))
    )
    (net (code "172") (name "unconnected-(U14A-PJ1-PadR7)") (class "Default")
      (node (ref "U14") (pin "R7") (pinfunction "PJ1_R7") (pintype "passive+no_connect"))
    )
    (net (code "173") (name "unconnected-(U14A-PJ3-PadN8)") (class "Default")
      (node (ref "U14") (pin "N8") (pinfunction "PJ3_N8") (pintype "passive+no_connect"))
    )
    (net (code "174") (name "unconnected-(U14A-PJ4-PadM9)") (class "Default")
      (node (ref "U14") (pin "M9") (pinfunction "PJ4_M9") (pintype "passive+no_connect"))
    )
    (net (code "175") (name "unconnected-(U14A-PJ12-PadB10)") (class "Default")
      (node (ref "U14") (pin "B10") (pinfunction "PJ12_B10") (pintype "passive+no_connect"))
    )
    (net (code "176") (name "unconnected-(U14A-PJ13-PadB9)") (class "Default")
      (node (ref "U14") (pin "B9") (pinfunction "PJ13_B9") (pintype "passive+no_connect"))
    )
    (net (code "177") (name "unconnected-(U14A-PJ14-PadC9)") (class "Default")
      (node (ref "U14") (pin "C9") (pinfunction "PJ14_C9") (pintype "passive+no_connect"))
    )
    (net (code "178") (name "unconnected-(U14A-PJ15-PadD10)") (class "Default")
      (node (ref "U14") (pin "D10") (pinfunction "PJ15_D10") (pintype "passive+no_connect"))
    )
    (net (code "179") (name "unconnected-(U14A-PK4-PadD7)") (class "Default")
      (node (ref "U14") (pin "D7") (pinfunction "PK4_D7") (pintype "passive+no_connect"))
    )
    (net (code "180") (name "unconnected-(U14A-PK5-PadC6)") (class "Default")
      (node (ref "U14") (pin "C6") (pinfunction "PK5_C6") (pintype "passive+no_connect"))
    )
    (net (code "181") (name "unconnected-(U14A-PK6-PadC5)") (class "Default")
      (node (ref "U14") (pin "C5") (pinfunction "PK6_C5") (pintype "passive+no_connect"))
    )
    (net (code "182") (name "unconnected-(U14A-PK7-PadC4)") (class "Default")
      (node (ref "U14") (pin "C4") (pinfunction "PK7_C4") (pintype "passive+no_connect"))
    )
    (net (code "183") (name "unconnected-(U14B-PD11-PadN10)") (class "Default")
      (node (ref "U14") (pin "N10") (pinfunction "PD11_N10") (pintype "passive+no_connect"))
    )
    (net (code "184") (name "unconnected-(U14B-PI8-ANTI_TAMP2-PadC2)") (class "Default")
      (node (ref "U14") (pin "C2") (pinfunction "PI8-ANTI_TAMP2_C2") (pintype "passive+no_connect"))
    )
    (net (code "185") (name "unconnected-(U14B-PI11-PadF3)") (class "Default")
      (node (ref "U14") (pin "F3") (pinfunction "PI11_F3") (pintype "passive+no_connect"))
    )
    (net (code "186") (name "unconnected-(U14B-PI12-PadE3)") (class "Default")
      (node (ref "U14") (pin "E3") (pinfunction "PI12_E3") (pintype "passive+no_connect"))
    )
    (net (code "187") (name "unconnected-(U14B-PI13-PadG3)") (class "Default")
      (node (ref "U14") (pin "G3") (pinfunction "PI13_G3") (pintype "passive+no_connect"))
    )
    (net (code "188") (name "unconnected-(U14B-PI14-PadH3)") (class "Default")
      (node (ref "U14") (pin "H3") (pinfunction "PI14_H3") (pintype "passive+no_connect"))
    )
    (net (code "189") (name "unconnected-(U14B-PI15-PadG4)") (class "Default")
      (node (ref "U14") (pin "G4") (pinfunction "PI15_G4") (pintype "passive+no_connect"))
    )
  )
)
